# Arduino_ESP8266_SHT21_BH1750.net
KiCad netlist of a schematic drawn in Altium Designer
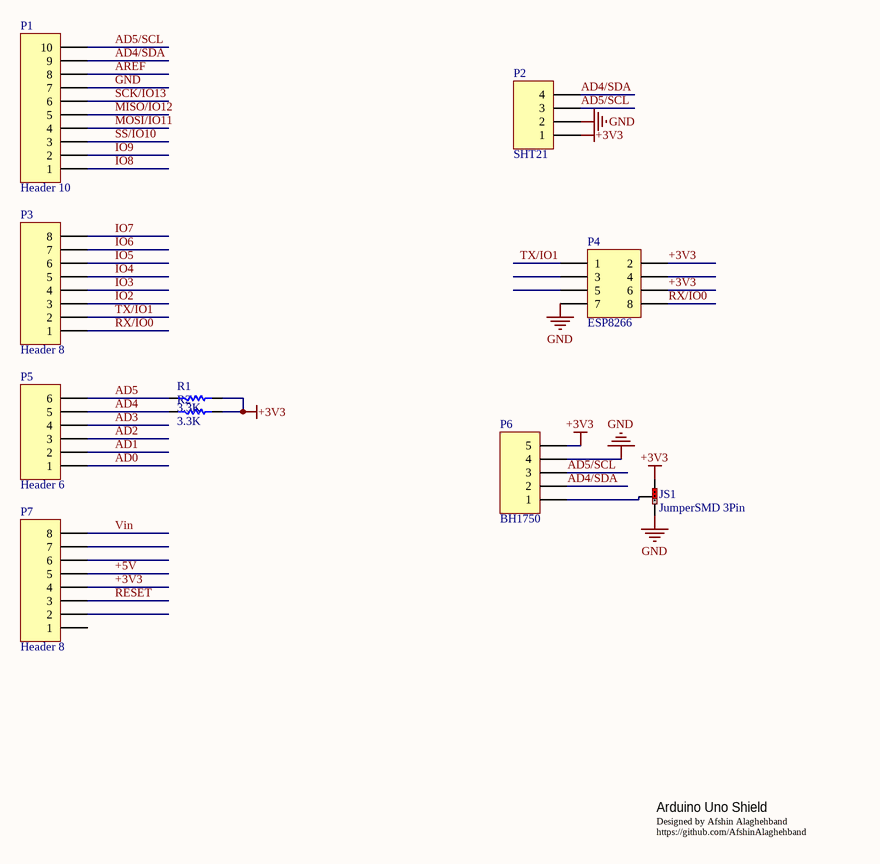
[diagram p0: Arduino_ESP8266_SHT21_BH1750.SchDoc]

(export (version "E")
  (design (tool "Eeschema 10.0.6"))
  (components
    (comp (ref "JS1")
      (value "JumperSMD 3Pin")
      (footprint "JumperSMD 3Pin - UltraSmall")
      (libsource (lib "R2T Team Library") (part "JumperSMD 3Pin"))
    )
    (comp (ref "P1")
      (value "Header 10")
      (footprint "HDR1X10")
      (description "Header, 10-Pin")
      (fields (field (name "PUBLISHER") "Altium Limited"))
      (libsource (lib "Miscellaneous Connectors") (part "Header 10"))
    )
    (comp (ref "P2")
      (value "SHT21")
      (footprint "HDR1X4")
      (description "SHT21 temperature and humidity sensor")
      (fields (field (name "PUBLISHER") "Altium Limited"))
      (libsource (lib "Miscellaneous Connectors") (part "Header 4"))
    )
    (comp (ref "P3")
      (value "Header 8")
      (footprint "HDR1X8")
      (description "Header, 8-Pin")
      (fields (field (name "PUBLISHER") "Altium Limited"))
      (libsource (lib "Miscellaneous Connectors") (part "Header 8"))
    )
    (comp (ref "P4")
      (value "ESP8266")
      (footprint "HDR2X4")
      (description "ESP8266-01")
      (fields (field (name "PUBLISHER") "Altium Limited"))
      (libsource (lib "Miscellaneous Connectors") (part "Header 4X2"))
    )
    (comp (ref "P5")
      (value "Header 6")
      (footprint "HDR1X6")
      (description "Header, 6-Pin")
      (fields (field (name "PUBLISHER") "Altium Limited"))
      (libsource (lib "Miscellaneous Connectors") (part "Header 6"))
    )
    (comp (ref "P6")
      (value "BH1750")
      (footprint "HDR1X5")
      (description "BH1750 Ambient Light Sensor")
      (fields (field (name "PUBLISHER") "Altium Limited"))
      (libsource (lib "Miscellaneous Connectors") (part "Header 5"))
    )
    (comp (ref "P7")
      (value "Header 8")
      (footprint "HDR1X8")
      (description "Header, 8-Pin")
      (fields (field (name "PUBLISHER") "Altium Limited"))
      (libsource (lib "Miscellaneous Connectors") (part "Header 8"))
    )
    (comp (ref "R1")
      (value "3.3K")
      (footprint "RES 0805 (2012X06L)")
      (description "Resistor")
      (fields (field (name "TOLERANCE") "5%") (field (name "POWER") "1/8 W"))
      (libsource (lib "My Library") (part "Resistor"))
    )
    (comp (ref "R2")
      (value "3.3K")
      (footprint "RES 0805 (2012X06L)")
      (description "Resistor")
      (fields (field (name "TOLERANCE") "5%") (field (name "POWER") "1/8 W"))
      (libsource (lib "My Library") (part "Resistor"))
    )
  )
  (nets
    (net (code "1") (name "+3V3") (class "Default")
      (node (ref "JS1") (pin "3") (pintype "passive"))
      (node (ref "P2") (pin "1") (pinfunction "1_1") (pintype "passive"))
      (node (ref "P4") (pin "2") (pinfunction "2_2") (pintype "passive"))
      (node (ref "P4") (pin "6") (pinfunction "6_6") (pintype "passive"))
      (node (ref "P6") (pin "5") (pinfunction "5_5") (pintype "passive"))
      (node (ref "P7") (pin "4") (pinfunction "4_4") (pintype "passive"))
      (node (ref "R1") (pin "2") (pinfunction "2_2") (pintype "passive"))
      (node (ref "R2") (pin "2") (pinfunction "2_2") (pintype "passive"))
    )
    (net (code "2") (name "/+5V") (class "Default")
      (node (ref "P7") (pin "5") (pinfunction "5_5") (pintype "passive"))
    )
    (net (code "3") (name "/AD0") (class "Default")
      (node (ref "P5") (pin "1") (pinfunction "1_1") (pintype "passive"))
    )
    (net (code "4") (name "/AD1") (class "Default")
      (node (ref "P5") (pin "2") (pinfunction "2_2") (pintype "passive"))
    )
    (net (code "5") (name "/AD2") (class "Default")
      (node (ref "P5") (pin "3") (pinfunction "3_3") (pintype "passive"))
    )
    (net (code "6") (name "/AD3") (class "Default")
      (node (ref "P5") (pin "4") (pinfunction "4_4") (pintype "passive"))
    )
    (net (code "7") (name "/AD4") (class "Default")
      (node (ref "P5") (pin "5") (pinfunction "5_5") (pintype "passive"))
      (node (ref "R2") (pin "1") (pinfunction "1_1") (pintype "passive"))
    )
    (net (code "8") (name "/AD4{slash}SDA") (class "Default")
      (node (ref "P1") (pin "9") (pinfunction "9_9") (pintype "passive"))
      (node (ref "P2") (pin "4") (pinfunction "4_4") (pintype "passive"))
      (node (ref "P6") (pin "2") (pinfunction "2_2") (pintype "passive"))
    )
    (net (code "9") (name "/AD5") (class "Default")
      (node (ref "P5") (pin "6") (pinfunction "6_6") (pintype "passive"))
      (node (ref "R1") (pin "1") (pinfunction "1_1") (pintype "passive"))
    )
    (net (code "10") (name "/AD5{slash}SCL") (class "Default")
      (node (ref "P1") (pin "10") (pinfunction "10_10") (pintype "passive"))
      (node (ref "P2") (pin "3") (pinfunction "3_3") (pintype "passive"))
      (node (ref "P6") (pin "3") (pinfunction "3_3") (pintype "passive"))
    )
    (net (code "11") (name "/AREF") (class "Default")
      (node (ref "P1") (pin "8") (pinfunction "8_8") (pintype "passive"))
    )
    (net (code "12") (name "/IO2") (class "Default")
      (node (ref "P3") (pin "3") (pinfunction "3_3") (pintype "passive"))
    )
    (net (code "13") (name "/IO3") (class "Default")
      (node (ref "P3") (pin "4") (pinfunction "4_4") (pintype "passive"))
    )
    (net (code "14") (name "/IO4") (class "Default")
      (node (ref "P3") (pin "5") (pinfunction "5_5") (pintype "passive"))
    )
    (net (code "15") (name "/IO5") (class "Default")
      (node (ref "P3") (pin "6") (pinfunction "6_6") (pintype "passive"))
    )
    (net (code "16") (name "/IO6") (class "Default")
      (node (ref "P3") (pin "7") (pinfunction "7_7") (pintype "passive"))
    )
    (net (code "17") (name "/IO7") (class "Default")
      (node (ref "P3") (pin "8") (pinfunction "8_8") (pintype "passive"))
    )
    (net (code "18") (name "/IO8") (class "Default")
      (node (ref "P1") (pin "1") (pinfunction "1_1") (pintype "passive"))
    )
    (net (code "19") (name "/IO9") (class "Default")
      (node (ref "P1") (pin "2") (pinfunction "2_2") (pintype "passive"))
    )
    (net (code "20") (name "/MISO{slash}IO12") (class "Default")
      (node (ref "P1") (pin "5") (pinfunction "5_5") (pintype "passive"))
    )
    (net (code "21") (name "/MOSI{slash}IO11") (class "Default")
      (node (ref "P1") (pin "4") (pinfunction "4_4") (pintype "passive"))
    )
    (net (code "22") (name "/RESET") (class "Default")
      (node (ref "P7") (pin "3") (pinfunction "3_3") (pintype "passive"))
    )
    (net (code "23") (name "/RX{slash}IO0") (class "Default")
      (node (ref "P3") (pin "1") (pinfunction "1_1") (pintype "passive"))
      (node (ref "P4") (pin "8") (pinfunction "8_8") (pintype "passive"))
    )
    (net (code "24") (name "/SCK{slash}IO13") (class "Default")
      (node (ref "P1") (pin "6") (pinfunction "6_6") (pintype "passive"))
    )
    (net (code "25") (name "/SS{slash}IO10") (class "Default")
      (node (ref "P1") (pin "3") (pinfunction "3_3") (pintype "passive"))
    )
    (net (code "26") (name "/TX{slash}IO1") (class "Default")
      (node (ref "P3") (pin "2") (pinfunction "2_2") (pintype "passive"))
      (node (ref "P4") (pin "1") (pinfunction "1_1") (pintype "passive"))
    )
    (net (code "27") (name "/Vin") (class "Default")
      (node (ref "P7") (pin "8") (pinfunction "8_8") (pintype "passive"))
    )
    (net (code "28") (name "GND") (class "Default")
      (node (ref "JS1") (pin "1") (pintype "passive"))
      (node (ref "P1") (pin "7") (pinfunction "7_7") (pintype "passive"))
      (node (ref "P2") (pin "2") (pinfunction "2_2") (pintype "passive"))
      (node (ref "P4") (pin "7") (pinfunction "7_7") (pintype "passive"))
      (node (ref "P6") (pin "4") (pinfunction "4_4") (pintype "passive"))
    )
    (net (code "29") (name "Net-(JS1-Pad2)") (class "Default")
      (node (ref "JS1") (pin "2") (pintype "passive"))
      (node (ref "P6") (pin "1") (pinfunction "1_1") (pintype "passive"))
    )
    (net (code "30") (name "unconnected-(P4-Pad3)") (class "Default")
      (node (ref "P4") (pin "3") (pinfunction "3_3") (pintype "passive"))
    )
    (net (code "31") (name "unconnected-(P4-Pad4)") (class "Default")
      (node (ref "P4") (pin "4") (pinfunction "4_4") (pintype "passive"))
    )
    (net (code "32") (name "unconnected-(P4-Pad5)") (class "Default")
      (node (ref "P4") (pin "5") (pinfunction "5_5") (pintype "passive"))
    )
    (net (code "33") (name "unconnected-(P7-Pad1)") (class "Default")
      (node (ref "P7") (pin "1") (pinfunction "1_1") (pintype "passive"))
    )
    (net (code "34") (name "unconnected-(P7-Pad2)") (class "Default")
      (node (ref "P7") (pin "2") (pinfunction "2_2") (pintype "passive"))
    )
    (net (code "35") (name "unconnected-(P7-Pad6)") (class "Default")
      (node (ref "P7") (pin "6") (pinfunction "6_6") (pintype "passive"))
    )
    (net (code "36") (name "unconnected-(P7-Pad7)") (class "Default")
      (node (ref "P7") (pin "7") (pinfunction "7_7") (pintype "passive"))
    )
  )
)
